# ATtiny84_ICSP-v7.net
KiCad netlist of a schematic drawn in EAGLE
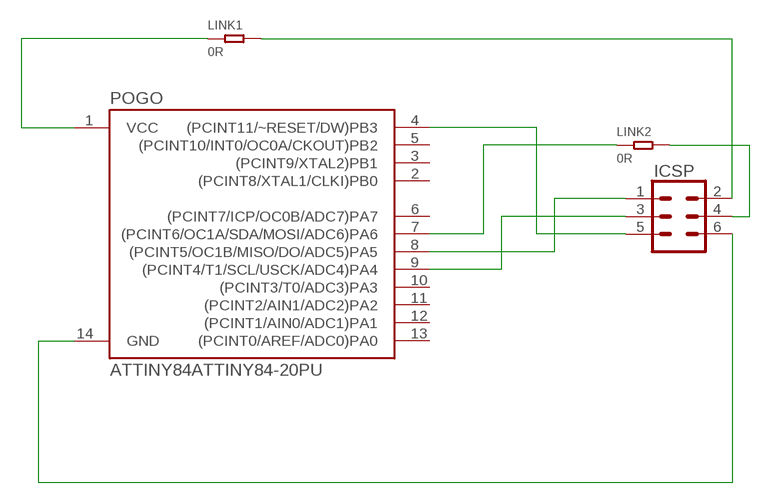
[diagram p0: schematic, sheet 1]

(export (version "E")
  (design (tool "Eeschema 10.0.6"))
  (components
    (comp (ref "ICSP")
      (value "CONN_03X2SHROUD")
      (footprint "eagle-import:2X3-SHROUDED")
      (libsource (lib "eagle-import") (part "CONN_03X2SHROUD"))
    )
    (comp (ref "LINK1")
      (value "0R")
      (footprint "eagle-import:PR-D2.3XL6.5MM")
      (fields (field (name "MPN") "FHCFR-1/4W-101J") (field (name "SPICEPREFIX") "L"))
      (libsource (lib "eagle-import") (part "DIP-RES-100R-5%-1/4W(PR-D2.3XL6.5MM)"))
    )
    (comp (ref "LINK2")
      (value "0R")
      (footprint "eagle-import:PR-D2.3XL6.5MM")
      (fields (field (name "MPN") "FHCFR-1/4W-101J") (field (name "SPICEPREFIX") "L"))
      (libsource (lib "eagle-import") (part "DIP-RES-100R-5%-1/4W(PR-D2.3XL6.5MM)"))
    )
    (comp (ref "POGO")
      (value "ATTINY84ATTINY84-20PU")
      (footprint "eagle-import:DIP14")
      (libsource (lib "eagle-import") (part "ATTINY84ATTINY84-20PU"))
    )
  )
  (nets
    (net (code "1") (name "Net-(ICSP-Pad2)") (class "Default")
      (node (ref "ICSP") (pin "2") (pinfunction "2_2") (pintype "bidirectional"))
      (node (ref "LINK1") (pin "2") (pinfunction "2_2") (pintype "passive"))
    )
    (net (code "2") (name "Net-(ICSP-Pad4)") (class "Default")
      (node (ref "ICSP") (pin "4") (pinfunction "4_4") (pintype "bidirectional"))
      (node (ref "LINK2") (pin "2") (pinfunction "2_2") (pintype "passive"))
    )
    (net (code "3") (name "Net-(POGO-(PCINT4{slash}T1{slash}SCL{slash}USCK{slash}ADC4)PA4)") (class "Default")
      (node (ref "ICSP") (pin "3") (pinfunction "3_3") (pintype "bidirectional"))
      (node (ref "POGO") (pin "9") (pinfunction "(PCINT4/T1/SCL/USCK/ADC4)PA4_9") (pintype "bidirectional"))
    )
    (net (code "4") (name "Net-(POGO-(PCINT5{slash}OC1B{slash}MISO{slash}DO{slash}ADC5)PA5)") (class "Default")
      (node (ref "ICSP") (pin "1") (pinfunction "1_1") (pintype "bidirectional"))
      (node (ref "POGO") (pin "8") (pinfunction "(PCINT5/OC1B/MISO/DO/ADC5)PA5_8") (pintype "bidirectional"))
    )
    (net (code "5") (name "Net-(POGO-(PCINT6{slash}OC1A{slash}SDA{slash}MOSI{slash}ADC6)PA6)") (class "Default")
      (node (ref "LINK2") (pin "1") (pinfunction "1_1") (pintype "passive"))
      (node (ref "POGO") (pin "7") (pinfunction "(PCINT6/OC1A/SDA/MOSI/ADC6)PA6_7") (pintype "bidirectional"))
    )
    (net (code "6") (name "Net-(POGO-(PCINT11{slash}~{RESET{slash}DW})PB3)") (class "Default")
      (node (ref "ICSP") (pin "5") (pinfunction "5_5") (pintype "bidirectional"))
      (node (ref "POGO") (pin "4") (pinfunction "(PCINT11/~{RESET/DW})PB3_4") (pintype "bidirectional"))
    )
    (net (code "7") (name "Net-(POGO-GND)") (class "Default")
      (node (ref "ICSP") (pin "6") (pinfunction "6_6") (pintype "bidirectional"))
      (node (ref "POGO") (pin "14") (pinfunction "GND_14") (pintype "bidirectional"))
    )
    (net (code "8") (name "Net-(POGO-VCC)") (class "Default")
      (node (ref "LINK1") (pin "1") (pinfunction "1_1") (pintype "passive"))
      (node (ref "POGO") (pin "1") (pinfunction "VCC_1") (pintype "bidirectional"))
    )
    (net (code "9") (name "unconnected-(POGO-(PCINT0{slash}AREF{slash}ADC0)PA0-Pad13)") (class "Default")
      (node (ref "POGO") (pin "13") (pinfunction "(PCINT0/AREF/ADC0)PA0_13") (pintype "bidirectional"))
    )
    (net (code "10") (name "unconnected-(POGO-(PCINT1{slash}AIN0{slash}ADC1)PA1-Pad12)") (class "Default")
      (node (ref "POGO") (pin "12") (pinfunction "(PCINT1/AIN0/ADC1)PA1_12") (pintype "bidirectional"))
    )
    (net (code "11") (name "unconnected-(POGO-(PCINT2{slash}AIN1{slash}ADC2)PA2-Pad11)") (class "Default")
      (node (ref "POGO") (pin "11") (pinfunction "(PCINT2/AIN1/ADC2)PA2_11") (pintype "bidirectional"))
    )
    (net (code "12") (name "unconnected-(POGO-(PCINT3{slash}T0{slash}ADC3)PA3-Pad10)") (class "Default")
      (node (ref "POGO") (pin "10") (pinfunction "(PCINT3/T0/ADC3)PA3_10") (pintype "bidirectional"))
    )
    (net (code "13") (name "unconnected-(POGO-(PCINT7{slash}ICP{slash}OC0B{slash}ADC7)PA7-Pad6)") (class "Default")
      (node (ref "POGO") (pin "6") (pinfunction "(PCINT7/ICP/OC0B/ADC7)PA7_6") (pintype "bidirectional"))
    )
    (net (code "14") (name "unconnected-(POGO-(PCINT8{slash}XTAL1{slash}CLKI)PB0-Pad2)") (class "Default")
      (node (ref "POGO") (pin "2") (pinfunction "(PCINT8/XTAL1/CLKI)PB0_2") (pintype "bidirectional"))
    )
    (net (code "15") (name "unconnected-(POGO-(PCINT9{slash}XTAL2)PB1-Pad3)") (class "Default")
      (node (ref "POGO") (pin "3") (pinfunction "(PCINT9/XTAL2)PB1_3") (pintype "bidirectional"))
    )
    (net (code "16") (name "unconnected-(POGO-(PCINT10{slash}INT0{slash}OC0A{slash}CKOUT)PB2-Pad5)") (class "Default")
      (node (ref "POGO") (pin "5") (pinfunction "(PCINT10/INT0/OC0A/CKOUT)PB2_5") (pintype "bidirectional"))
    )
  )
)
